# shield_mega_seed4_mpu_lobo5.net
KiCad netlist of a schematic drawn in EAGLE
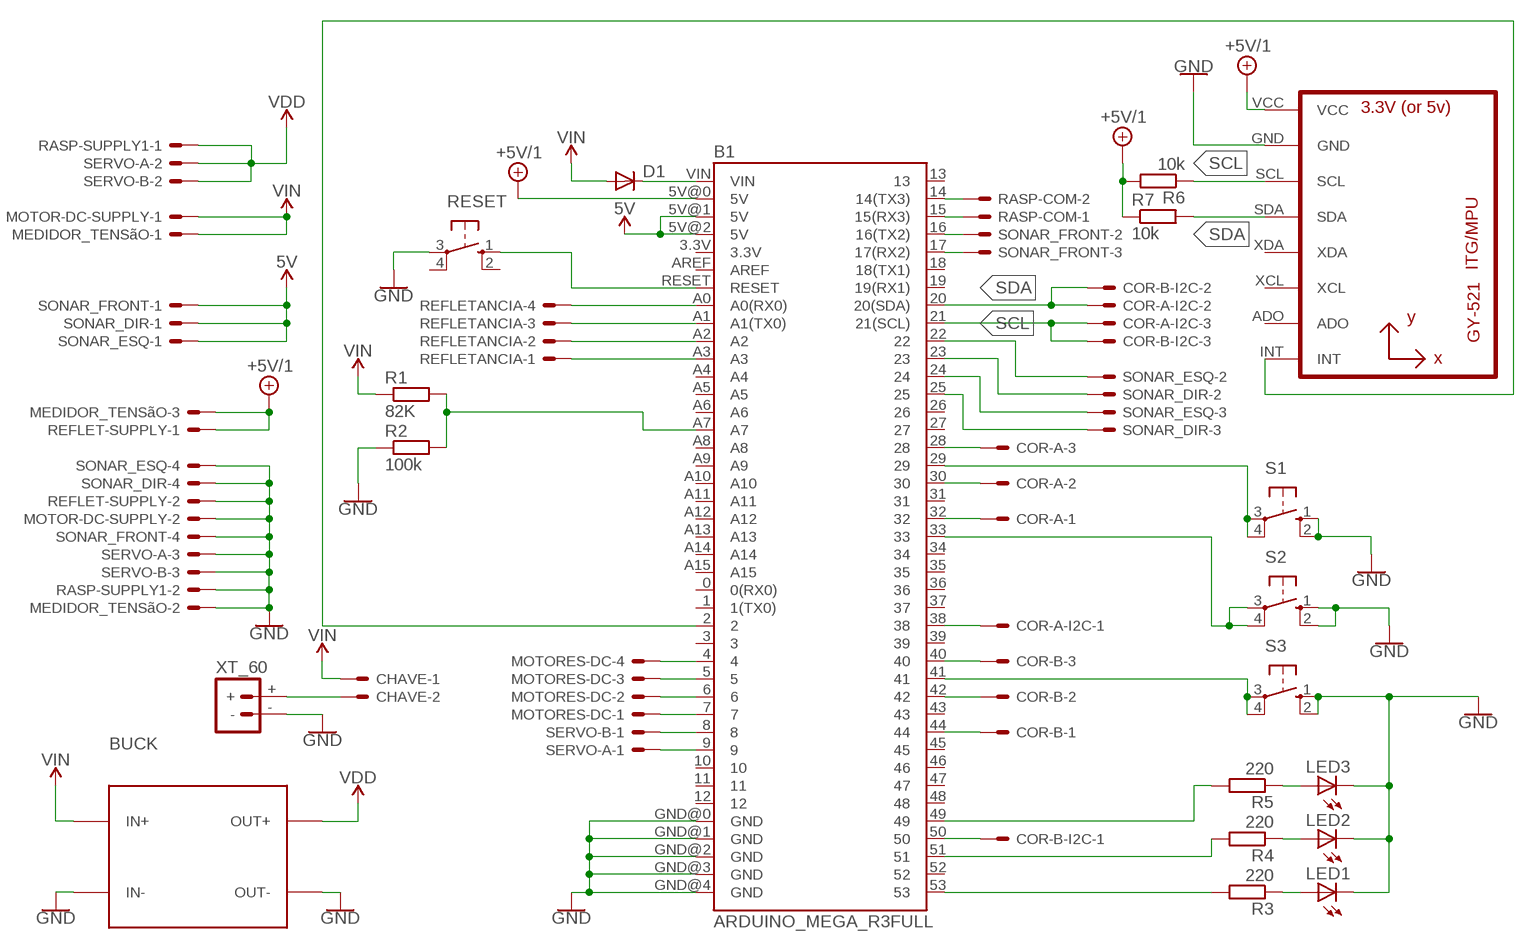
[diagram p0: schematic, sheet 1]

(export (version "E")
  (design (tool "Eeschema 10.0.6"))
  (components
    (comp (ref "B1")
      (value "ARDUINO_MEGA_R3FULL")
      (footprint "eagle-import:ARDUINO_MEGA")
      (libsource (lib "eagle-import") (part "ARDUINO_MEGA_R3FULL"))
    )
    (comp (ref "BUCK")
      (value "DC-DC-STEP-DOWN-LM2596")
      (footprint "eagle-import:DC-DC-STEP-DOWN-LM2596")
      (libsource (lib "eagle-import") (part "DC-DC-STEP-DOWN-LM2596"))
    )
    (comp (ref "CHAVE")
      (value "22-23-2021")
      (footprint "eagle-import:22-23-2021")
      (fields (field (name "MF") "MOLEX"))
      (libsource (lib "eagle-import") (part "22-23-2021"))
    )
    (comp (ref "COR-A")
      (value "22-23-2031")
      (footprint "eagle-import:22-23-2031")
      (fields (field (name "MF") "MOLEX"))
      (libsource (lib "eagle-import") (part "22-23-2031"))
    )
    (comp (ref "COR-A-I2C")
      (value "22-23-2031")
      (footprint "eagle-import:22-23-2031")
      (fields (field (name "MF") "MOLEX"))
      (libsource (lib "eagle-import") (part "22-23-2031"))
    )
    (comp (ref "COR-B")
      (value "22-23-2031")
      (footprint "eagle-import:22-23-2031")
      (fields (field (name "MF") "MOLEX"))
      (libsource (lib "eagle-import") (part "22-23-2031"))
    )
    (comp (ref "COR-B-I2C")
      (value "22-23-2031")
      (footprint "eagle-import:22-23-2031")
      (fields (field (name "MF") "MOLEX"))
      (libsource (lib "eagle-import") (part "22-23-2031"))
    )
    (comp (ref "D1")
      (value "1N4004")
      (footprint "eagle-import:DO41-10")
      (libsource (lib "eagle-import") (part "1N4004"))
    )
    (comp (ref "LED1")
      (value "LED5MM")
      (footprint "eagle-import:LED5MM")
      (libsource (lib "eagle-import") (part "LED5MM"))
    )
    (comp (ref "LED2")
      (value "LED5MM")
      (footprint "eagle-import:LED5MM")
      (libsource (lib "eagle-import") (part "LED5MM"))
    )
    (comp (ref "LED3")
      (value "LED5MM")
      (footprint "eagle-import:LED5MM")
      (libsource (lib "eagle-import") (part "LED5MM"))
    )
    (comp (ref "MEDIDOR_TENSãO")
      (value "22-23-2031")
      (footprint "eagle-import:22-23-2031")
      (fields (field (name "MF") "MOLEX"))
      (libsource (lib "eagle-import") (part "22-23-2031"))
    )
    (comp (ref "MOTOR-DC-SUPPLY")
      (value "22-23-2021")
      (footprint "eagle-import:22-23-2021")
      (fields (field (name "MF") "MOLEX"))
      (libsource (lib "eagle-import") (part "22-23-2021"))
    )
    (comp (ref "MOTORES-DC")
      (value "22-23-2041")
      (footprint "eagle-import:22-23-2041")
      (fields (field (name "MF") "MOLEX"))
      (libsource (lib "eagle-import") (part "22-23-2041"))
    )
    (comp (ref "R1")
      (value "82K")
      (footprint "eagle-import:0207_12")
      (libsource (lib "eagle-import") (part "R-EU_0207/12"))
    )
    (comp (ref "R2")
      (value "100k")
      (footprint "eagle-import:0207_12")
      (libsource (lib "eagle-import") (part "R-EU_0207/12"))
    )
    (comp (ref "R3")
      (value "220")
      (footprint "eagle-import:0207_7")
      (libsource (lib "eagle-import") (part "R-EU_0207/7"))
    )
    (comp (ref "R4")
      (value "220")
      (footprint "eagle-import:0207_7")
      (libsource (lib "eagle-import") (part "R-EU_0207/7"))
    )
    (comp (ref "R5")
      (value "220")
      (footprint "eagle-import:0207_7")
      (libsource (lib "eagle-import") (part "R-EU_0207/7"))
    )
    (comp (ref "R6")
      (value "10k")
      (footprint "eagle-import:0204_7")
      (libsource (lib "eagle-import") (part "R-EU_0204/7"))
    )
    (comp (ref "R7")
      (value "10k")
      (footprint "eagle-import:0204_7")
      (libsource (lib "eagle-import") (part "R-EU_0204/7"))
    )
    (comp (ref "RASP-COM")
      (value "22-23-2021")
      (footprint "eagle-import:22-23-2021")
      (fields (field (name "MF") "MOLEX"))
      (libsource (lib "eagle-import") (part "22-23-2021"))
    )
    (comp (ref "RASP-SUPPLY1")
      (value "22-23-2021")
      (footprint "eagle-import:22-23-2021")
      (fields (field (name "MF") "MOLEX"))
      (libsource (lib "eagle-import") (part "22-23-2021"))
    )
    (comp (ref "REFLET-SUPPLY")
      (value "22-23-2021")
      (footprint "eagle-import:22-23-2021")
      (fields (field (name "MF") "MOLEX"))
      (libsource (lib "eagle-import") (part "22-23-2021"))
    )
    (comp (ref "REFLETANCIA")
      (value "22-23-2041")
      (footprint "eagle-import:22-23-2041")
      (fields (field (name "MF") "MOLEX"))
      (libsource (lib "eagle-import") (part "22-23-2041"))
    )
    (comp (ref "RESET")
      (value "10-XX")
      (footprint "eagle-import:B3F-10XX")
      (fields (field (name "MPN") "B3F-1000"))
      (libsource (lib "eagle-import") (part "10-XX"))
    )
    (comp (ref "S1")
      (value "10-XX")
      (footprint "eagle-import:B3F-10XX")
      (fields (field (name "MPN") "B3F-1000"))
      (libsource (lib "eagle-import") (part "10-XX"))
    )
    (comp (ref "S2")
      (value "10-XX")
      (footprint "eagle-import:B3F-10XX")
      (fields (field (name "MPN") "B3F-1000"))
      (libsource (lib "eagle-import") (part "10-XX"))
    )
    (comp (ref "S3")
      (value "10-XX")
      (footprint "eagle-import:B3F-10XX")
      (fields (field (name "MPN") "B3F-1000"))
      (libsource (lib "eagle-import") (part "10-XX"))
    )
    (comp (ref "SERVO-A")
      (value "22-23-2031")
      (footprint "eagle-import:22-23-2031")
      (fields (field (name "MF") "MOLEX"))
      (libsource (lib "eagle-import") (part "22-23-2031"))
    )
    (comp (ref "SERVO-B")
      (value "22-23-2031")
      (footprint "eagle-import:22-23-2031")
      (fields (field (name "MF") "MOLEX"))
      (libsource (lib "eagle-import") (part "22-23-2031"))
    )
    (comp (ref "SONAR_DIR")
      (value "22-23-2041")
      (footprint "eagle-import:22-23-2041")
      (fields (field (name "MF") "MOLEX"))
      (libsource (lib "eagle-import") (part "22-23-2041"))
    )
    (comp (ref "SONAR_ESQ")
      (value "22-23-2041")
      (footprint "eagle-import:22-23-2041")
      (fields (field (name "MF") "MOLEX"))
      (libsource (lib "eagle-import") (part "22-23-2041"))
    )
    (comp (ref "SONAR_FRONT")
      (value "22-23-2041")
      (footprint "eagle-import:22-23-2041")
      (fields (field (name "MF") "MOLEX"))
      (libsource (lib "eagle-import") (part "22-23-2041"))
    )
    (comp (ref "U1")
      (value "GY-521MPU6050")
      (footprint "eagle-import:GY-521")
      (libsource (lib "eagle-import") (part "GY-521MPU6050"))
    )
    (comp (ref "XT_60")
      (value "BATTERY_CONNXT60")
      (footprint "eagle-import:XT60")
      (libsource (lib "eagle-import") (part "BATTERY_CONNXT60"))
    )
  )
  (nets
    (net (code "1") (name "+5V{slash}1") (class "Default")
      (node (ref "B1") (pin "5V@0") (pinfunction "5V_5V@0") (pintype "bidirectional"))
      (node (ref "MEDIDOR_TENSãO") (pin "3") (pinfunction "S_3") (pintype "passive"))
      (node (ref "R6") (pin "2") (pinfunction "2_2") (pintype "passive"))
      (node (ref "R7") (pin "1") (pinfunction "1_1") (pintype "passive"))
      (node (ref "REFLET-SUPPLY") (pin "1") (pinfunction "S_1") (pintype "passive"))
      (node (ref "U1") (pin "VCC") (pinfunction "VCC_VCC") (pintype "bidirectional"))
    )
    (net (code "2") (name "5V") (class "Default")
      (node (ref "B1") (pin "5V@1") (pinfunction "5V_5V@1") (pintype "bidirectional"))
      (node (ref "B1") (pin "5V@2") (pinfunction "5V_5V@2") (pintype "bidirectional"))
      (node (ref "SONAR_DIR") (pin "1") (pinfunction "S_1") (pintype "passive"))
      (node (ref "SONAR_ESQ") (pin "1") (pinfunction "S_1") (pintype "passive"))
      (node (ref "SONAR_FRONT") (pin "1") (pinfunction "S_1") (pintype "passive"))
    )
    (net (code "3") (name "GND") (class "Default")
      (node (ref "B1") (pin "GND@0") (pinfunction "GND_GND@0") (pintype "bidirectional"))
      (node (ref "B1") (pin "GND@1") (pinfunction "GND_GND@1") (pintype "bidirectional"))
      (node (ref "B1") (pin "GND@2") (pinfunction "GND_GND@2") (pintype "bidirectional"))
      (node (ref "B1") (pin "GND@3") (pinfunction "GND_GND@3") (pintype "bidirectional"))
      (node (ref "B1") (pin "GND@4") (pinfunction "GND_GND@4") (pintype "bidirectional"))
      (node (ref "BUCK") (pin "IN-") (pinfunction "IN-_IN-") (pintype "bidirectional"))
      (node (ref "BUCK") (pin "OUT-") (pinfunction "OUT-_OUT-") (pintype "bidirectional"))
      (node (ref "LED1") (pin "K") (pinfunction "C_K") (pintype "passive"))
      (node (ref "LED2") (pin "K") (pinfunction "C_K") (pintype "passive"))
      (node (ref "LED3") (pin "K") (pinfunction "C_K") (pintype "passive"))
      (node (ref "MEDIDOR_TENSãO") (pin "2") (pinfunction "S_2") (pintype "passive"))
      (node (ref "MOTOR-DC-SUPPLY") (pin "2") (pinfunction "S_2") (pintype "passive"))
      (node (ref "R2") (pin "1") (pinfunction "1_1") (pintype "passive"))
      (node (ref "RASP-SUPPLY1") (pin "2") (pinfunction "S_2") (pintype "passive"))
      (node (ref "REFLET-SUPPLY") (pin "2") (pinfunction "S_2") (pintype "passive"))
      (node (ref "RESET") (pin "3") (pinfunction "P_3") (pintype "passive"))
      (node (ref "S1") (pin "1") (pinfunction "S_1") (pintype "passive"))
      (node (ref "S1") (pin "2") (pinfunction "S1_2") (pintype "passive"))
      (node (ref "S2") (pin "1") (pinfunction "S_1") (pintype "passive"))
      (node (ref "S2") (pin "2") (pinfunction "S1_2") (pintype "passive"))
      (node (ref "S3") (pin "1") (pinfunction "S_1") (pintype "passive"))
      (node (ref "S3") (pin "2") (pinfunction "S1_2") (pintype "passive"))
      (node (ref "SERVO-A") (pin "3") (pinfunction "S_3") (pintype "passive"))
      (node (ref "SERVO-B") (pin "3") (pinfunction "S_3") (pintype "passive"))
      (node (ref "SONAR_DIR") (pin "4") (pinfunction "S_4") (pintype "passive"))
      (node (ref "SONAR_ESQ") (pin "4") (pinfunction "S_4") (pintype "passive"))
      (node (ref "SONAR_FRONT") (pin "4") (pinfunction "S_4") (pintype "passive"))
      (node (ref "U1") (pin "GND") (pinfunction "GND_GND") (pintype "bidirectional"))
      (node (ref "XT_60") (pin "-") (pinfunction "-_-") (pintype "passive"))
    )
    (net (code "4") (name "Net-(B1-14(TX3))") (class "Default")
      (node (ref "B1") (pin "14") (pinfunction "14(TX3)_14") (pintype "bidirectional"))
      (node (ref "RASP-COM") (pin "2") (pinfunction "S_2") (pintype "passive"))
    )
    (net (code "5") (name "Net-(B1-15(RX3))") (class "Default")
      (node (ref "B1") (pin "15") (pinfunction "15(RX3)_15") (pintype "bidirectional"))
      (node (ref "RASP-COM") (pin "1") (pinfunction "S_1") (pintype "passive"))
    )
    (net (code "6") (name "Net-(B1-16(TX2))") (class "Default")
      (node (ref "B1") (pin "16") (pinfunction "16(TX2)_16") (pintype "bidirectional"))
      (node (ref "SONAR_FRONT") (pin "2") (pinfunction "S_2") (pintype "passive"))
    )
    (net (code "7") (name "Net-(B1-17(RX2))") (class "Default")
      (node (ref "B1") (pin "17") (pinfunction "17(RX2)_17") (pintype "bidirectional"))
      (node (ref "SONAR_FRONT") (pin "3") (pinfunction "S_3") (pintype "passive"))
    )
    (net (code "8") (name "Net-(B1-A0(RX0))") (class "Default")
      (node (ref "B1") (pin "A0") (pinfunction "A0(RX0)_A0") (pintype "bidirectional"))
      (node (ref "REFLETANCIA") (pin "4") (pinfunction "S_4") (pintype "passive"))
    )
    (net (code "9") (name "Net-(B1-A1(TX0))") (class "Default")
      (node (ref "B1") (pin "A1") (pinfunction "A1(TX0)_A1") (pintype "bidirectional"))
      (node (ref "REFLETANCIA") (pin "3") (pinfunction "S_3") (pintype "passive"))
    )
    (net (code "10") (name "Net-(B1-Pad2)") (class "Default")
      (node (ref "B1") (pin "2") (pinfunction "2_2") (pintype "bidirectional"))
      (node (ref "U1") (pin "INT") (pinfunction "INT_INT") (pintype "bidirectional"))
    )
    (net (code "11") (name "Net-(B1-Pad49)") (class "Default")
      (node (ref "B1") (pin "49") (pinfunction "49_49") (pintype "bidirectional"))
      (node (ref "R5") (pin "2") (pinfunction "2_2") (pintype "passive"))
    )
    (net (code "12") (name "Net-(B1-Pad51)") (class "Default")
      (node (ref "B1") (pin "51") (pinfunction "51_51") (pintype "bidirectional"))
      (node (ref "R4") (pin "2") (pinfunction "2_2") (pintype "passive"))
    )
    (net (code "13") (name "Net-(B1-Pad53)") (class "Default")
      (node (ref "B1") (pin "53") (pinfunction "53_53") (pintype "bidirectional"))
      (node (ref "R3") (pin "2") (pinfunction "2_2") (pintype "passive"))
    )
    (net (code "14") (name "Net-(B1-PadA7)") (class "Default")
      (node (ref "B1") (pin "A7") (pinfunction "A7_A7") (pintype "bidirectional"))
      (node (ref "R1") (pin "2") (pinfunction "2_2") (pintype "passive"))
      (node (ref "R2") (pin "2") (pinfunction "2_2") (pintype "passive"))
    )
    (net (code "15") (name "Net-(B1-PadVIN)") (class "Default")
      (node (ref "B1") (pin "VIN") (pinfunction "VIN_VIN") (pintype "bidirectional"))
      (node (ref "D1") (pin "C") (pinfunction "C_C") (pintype "passive"))
    )
    (net (code "16") (name "Net-(CHAVEB-S)") (class "Default")
      (node (ref "CHAVE") (pin "2") (pinfunction "S_2") (pintype "passive"))
      (node (ref "XT_60") (pin "+") (pinfunction "+_+") (pintype "passive"))
    )
    (net (code "17") (name "Net-(COR-A-I2CA-S)") (class "Default")
      (node (ref "B1") (pin "38") (pinfunction "38_38") (pintype "bidirectional"))
      (node (ref "COR-A-I2C") (pin "1") (pinfunction "S_1") (pintype "passive"))
    )
    (net (code "18") (name "Net-(COR-AA-S)") (class "Default")
      (node (ref "B1") (pin "32") (pinfunction "32_32") (pintype "bidirectional"))
      (node (ref "COR-A") (pin "1") (pinfunction "S_1") (pintype "passive"))
    )
    (net (code "19") (name "Net-(COR-AB-S)") (class "Default")
      (node (ref "B1") (pin "30") (pinfunction "30_30") (pintype "bidirectional"))
      (node (ref "COR-A") (pin "2") (pinfunction "S_2") (pintype "passive"))
    )
    (net (code "20") (name "Net-(COR-AC-S)") (class "Default")
      (node (ref "B1") (pin "28") (pinfunction "28_28") (pintype "bidirectional"))
      (node (ref "COR-A") (pin "3") (pinfunction "S_3") (pintype "passive"))
    )
    (net (code "21") (name "Net-(COR-B-I2CA-S)") (class "Default")
      (node (ref "B1") (pin "50") (pinfunction "50_50") (pintype "bidirectional"))
      (node (ref "COR-B-I2C") (pin "1") (pinfunction "S_1") (pintype "passive"))
    )
    (net (code "22") (name "Net-(COR-BA-S)") (class "Default")
      (node (ref "B1") (pin "44") (pinfunction "44_44") (pintype "bidirectional"))
      (node (ref "COR-B") (pin "1") (pinfunction "S_1") (pintype "passive"))
    )
    (net (code "23") (name "Net-(COR-BB-S)") (class "Default")
      (node (ref "B1") (pin "42") (pinfunction "42_42") (pintype "bidirectional"))
      (node (ref "COR-B") (pin "2") (pinfunction "S_2") (pintype "passive"))
    )
    (net (code "24") (name "Net-(COR-BC-S)") (class "Default")
      (node (ref "B1") (pin "40") (pinfunction "40_40") (pintype "bidirectional"))
      (node (ref "COR-B") (pin "3") (pinfunction "S_3") (pintype "passive"))
    )
    (net (code "25") (name "Net-(LED1-PadA)") (class "Default")
      (node (ref "LED1") (pin "A") (pinfunction "A_A") (pintype "passive"))
      (node (ref "R3") (pin "1") (pinfunction "1_1") (pintype "passive"))
    )
    (net (code "26") (name "Net-(LED2-PadA)") (class "Default")
      (node (ref "LED2") (pin "A") (pinfunction "A_A") (pintype "passive"))
      (node (ref "R4") (pin "1") (pinfunction "1_1") (pintype "passive"))
    )
    (net (code "27") (name "Net-(LED3-PadA)") (class "Default")
      (node (ref "LED3") (pin "A") (pinfunction "A_A") (pintype "passive"))
      (node (ref "R5") (pin "1") (pinfunction "1_1") (pintype "passive"))
    )
    (net (code "28") (name "Net-(MOTORES-DCA-S)") (class "Default")
      (node (ref "B1") (pin "7") (pinfunction "7_7") (pintype "bidirectional"))
      (node (ref "MOTORES-DC") (pin "1") (pinfunction "S_1") (pintype "passive"))
    )
    (net (code "29") (name "Net-(MOTORES-DCB-S)") (class "Default")
      (node (ref "B1") (pin "6") (pinfunction "6_6") (pintype "bidirectional"))
      (node (ref "MOTORES-DC") (pin "2") (pinfunction "S_2") (pintype "passive"))
    )
    (net (code "30") (name "Net-(MOTORES-DCC-S)") (class "Default")
      (node (ref "B1") (pin "5") (pinfunction "5_5") (pintype "bidirectional"))
      (node (ref "MOTORES-DC") (pin "3") (pinfunction "S_3") (pintype "passive"))
    )
    (net (code "31") (name "Net-(MOTORES-DCD-S)") (class "Default")
      (node (ref "B1") (pin "4") (pinfunction "4_4") (pintype "bidirectional"))
      (node (ref "MOTORES-DC") (pin "4") (pinfunction "S_4") (pintype "passive"))
    )
    (net (code "32") (name "Net-(REFLETANCIAA-S)") (class "Default")
      (node (ref "B1") (pin "A3") (pinfunction "A3_A3") (pintype "bidirectional"))
      (node (ref "REFLETANCIA") (pin "1") (pinfunction "S_1") (pintype "passive"))
    )
    (net (code "33") (name "Net-(REFLETANCIAB-S)") (class "Default")
      (node (ref "B1") (pin "A2") (pinfunction "A2_A2") (pintype "bidirectional"))
      (node (ref "REFLETANCIA") (pin "2") (pinfunction "S_2") (pintype "passive"))
    )
    (net (code "34") (name "Net-(RESET-S)") (class "Default")
      (node (ref "B1") (pin "RESET") (pinfunction "RESET_RESET") (pintype "bidirectional"))
      (node (ref "RESET") (pin "1") (pinfunction "S_1") (pintype "passive"))
    )
    (net (code "35") (name "Net-(S1-P)") (class "Default")
      (node (ref "B1") (pin "29") (pinfunction "29_29") (pintype "bidirectional"))
      (node (ref "S1") (pin "3") (pinfunction "P_3") (pintype "passive"))
      (node (ref "S1") (pin "4") (pinfunction "P1_4") (pintype "passive"))
    )
    (net (code "36") (name "Net-(S2-P)") (class "Default")
      (node (ref "B1") (pin "33") (pinfunction "33_33") (pintype "bidirectional"))
      (node (ref "S2") (pin "3") (pinfunction "P_3") (pintype "passive"))
      (node (ref "S2") (pin "4") (pinfunction "P1_4") (pintype "passive"))
    )
    (net (code "37") (name "Net-(S3-P)") (class "Default")
      (node (ref "B1") (pin "41") (pinfunction "41_41") (pintype "bidirectional"))
      (node (ref "S3") (pin "3") (pinfunction "P_3") (pintype "passive"))
      (node (ref "S3") (pin "4") (pinfunction "P1_4") (pintype "passive"))
    )
    (net (code "38") (name "Net-(SERVO-AA-S)") (class "Default")
      (node (ref "B1") (pin "9") (pinfunction "9_9") (pintype "bidirectional"))
      (node (ref "SERVO-A") (pin "1") (pinfunction "S_1") (pintype "passive"))
    )
    (net (code "39") (name "Net-(SERVO-BA-S)") (class "Default")
      (node (ref "B1") (pin "8") (pinfunction "8_8") (pintype "bidirectional"))
      (node (ref "SERVO-B") (pin "1") (pinfunction "S_1") (pintype "passive"))
    )
    (net (code "40") (name "Net-(SONAR_DIRB-S)") (class "Default")
      (node (ref "B1") (pin "23") (pinfunction "23_23") (pintype "bidirectional"))
      (node (ref "SONAR_DIR") (pin "2") (pinfunction "S_2") (pintype "passive"))
    )
    (net (code "41") (name "Net-(SONAR_DIRC-S)") (class "Default")
      (node (ref "B1") (pin "25") (pinfunction "25_25") (pintype "bidirectional"))
      (node (ref "SONAR_DIR") (pin "3") (pinfunction "S_3") (pintype "passive"))
    )
    (net (code "42") (name "Net-(SONAR_ESQB-S)") (class "Default")
      (node (ref "B1") (pin "22") (pinfunction "22_22") (pintype "bidirectional"))
      (node (ref "SONAR_ESQ") (pin "2") (pinfunction "S_2") (pintype "passive"))
    )
    (net (code "43") (name "Net-(SONAR_ESQC-S)") (class "Default")
      (node (ref "B1") (pin "24") (pinfunction "24_24") (pintype "bidirectional"))
      (node (ref "SONAR_ESQ") (pin "3") (pinfunction "S_3") (pintype "passive"))
    )
    (net (code "44") (name "SCL") (class "Default")
      (node (ref "B1") (pin "21") (pinfunction "21(SCL)_21") (pintype "bidirectional"))
      (node (ref "COR-A-I2C") (pin "3") (pinfunction "S_3") (pintype "passive"))
      (node (ref "COR-B-I2C") (pin "3") (pinfunction "S_3") (pintype "passive"))
      (node (ref "R6") (pin "1") (pinfunction "1_1") (pintype "passive"))
      (node (ref "U1") (pin "SCL") (pinfunction "SCL_SCL") (pintype "bidirectional"))
    )
    (net (code "45") (name "SDA") (class "Default")
      (node (ref "B1") (pin "20") (pinfunction "20(SDA)_20") (pintype "bidirectional"))
      (node (ref "COR-A-I2C") (pin "2") (pinfunction "S_2") (pintype "passive"))
      (node (ref "COR-B-I2C") (pin "2") (pinfunction "S_2") (pintype "passive"))
      (node (ref "R7") (pin "2") (pinfunction "2_2") (pintype "passive"))
      (node (ref "U1") (pin "SDA") (pinfunction "SDA_SDA") (pintype "bidirectional"))
    )
    (net (code "46") (name "VDD") (class "Default")
      (node (ref "BUCK") (pin "OUT+") (pinfunction "OUT+_OUT+") (pintype "bidirectional"))
      (node (ref "RASP-SUPPLY1") (pin "1") (pinfunction "S_1") (pintype "passive"))
      (node (ref "SERVO-A") (pin "2") (pinfunction "S_2") (pintype "passive"))
      (node (ref "SERVO-B") (pin "2") (pinfunction "S_2") (pintype "passive"))
    )
    (net (code "47") (name "VIN") (class "Default")
      (node (ref "BUCK") (pin "IN+") (pinfunction "IN+_IN+") (pintype "bidirectional"))
      (node (ref "CHAVE") (pin "1") (pinfunction "S_1") (pintype "passive"))
      (node (ref "D1") (pin "A") (pinfunction "A_A") (pintype "passive"))
      (node (ref "MEDIDOR_TENSãO") (pin "1") (pinfunction "S_1") (pintype "passive"))
      (node (ref "MOTOR-DC-SUPPLY") (pin "1") (pinfunction "S_1") (pintype "passive"))
      (node (ref "R1") (pin "1") (pinfunction "1_1") (pintype "passive"))
    )
    (net (code "48") (name "unconnected-(B1-0(RX0)-Pad0)") (class "Default")
      (node (ref "B1") (pin "0") (pinfunction "0(RX0)_0") (pintype "bidirectional"))
    )
    (net (code "49") (name "unconnected-(B1-1(TX0)-Pad1)") (class "Default")
      (node (ref "B1") (pin "1") (pinfunction "1(TX0)_1") (pintype "bidirectional"))
    )
    (net (code "50") (name "unconnected-(B1-18(TX1)-Pad18)") (class "Default")
      (node (ref "B1") (pin "18") (pinfunction "18(TX1)_18") (pintype "bidirectional"))
    )
    (net (code "51") (name "unconnected-(B1-19(RX1)-Pad19)") (class "Default")
      (node (ref "B1") (pin "19") (pinfunction "19(RX1)_19") (pintype "bidirectional"))
    )
    (net (code "52") (name "unconnected-(B1-Pad3)") (class "Default")
      (node (ref "B1") (pin "3") (pinfunction "3_3") (pintype "bidirectional"))
    )
    (net (code "53") (name "unconnected-(B1-Pad3.3V)") (class "Default")
      (node (ref "B1") (pin "3.3V") (pinfunction "3.3V_3.3V") (pintype "bidirectional"))
    )
    (net (code "54") (name "unconnected-(B1-Pad10)") (class "Default")
      (node (ref "B1") (pin "10") (pinfunction "10_10") (pintype "bidirectional"))
    )
    (net (code "55") (name "unconnected-(B1-Pad11)") (class "Default")
      (node (ref "B1") (pin "11") (pinfunction "11_11") (pintype "bidirectional"))
    )
    (net (code "56") (name "unconnected-(B1-Pad12)") (class "Default")
      (node (ref "B1") (pin "12") (pinfunction "12_12") (pintype "bidirectional"))
    )
    (net (code "57") (name "unconnected-(B1-Pad13)") (class "Default")
      (node (ref "B1") (pin "13") (pinfunction "13_13") (pintype "bidirectional"))
    )
    (net (code "58") (name "unconnected-(B1-Pad26)") (class "Default")
      (node (ref "B1") (pin "26") (pinfunction "26_26") (pintype "bidirectional"))
    )
    (net (code "59") (name "unconnected-(B1-Pad27)") (class "Default")
      (node (ref "B1") (pin "27") (pinfunction "27_27") (pintype "bidirectional"))
    )
    (net (code "60") (name "unconnected-(B1-Pad31)") (class "Default")
      (node (ref "B1") (pin "31") (pinfunction "31_31") (pintype "bidirectional"))
    )
    (net (code "61") (name "unconnected-(B1-Pad34)") (class "Default")
      (node (ref "B1") (pin "34") (pinfunction "34_34") (pintype "bidirectional"))
    )
    (net (code "62") (name "unconnected-(B1-Pad35)") (class "Default")
      (node (ref "B1") (pin "35") (pinfunction "35_35") (pintype "bidirectional"))
    )
    (net (code "63") (name "unconnected-(B1-Pad36)") (class "Default")
      (node (ref "B1") (pin "36") (pinfunction "36_36") (pintype "bidirectional"))
    )
    (net (code "64") (name "unconnected-(B1-Pad37)") (class "Default")
      (node (ref "B1") (pin "37") (pinfunction "37_37") (pintype "bidirectional"))
    )
    (net (code "65") (name "unconnected-(B1-Pad39)") (class "Default")
      (node (ref "B1") (pin "39") (pinfunction "39_39") (pintype "bidirectional"))
    )
    (net (code "66") (name "unconnected-(B1-Pad43)") (class "Default")
      (node (ref "B1") (pin "43") (pinfunction "43_43") (pintype "bidirectional"))
    )
    (net (code "67") (name "unconnected-(B1-Pad45)") (class "Default")
      (node (ref "B1") (pin "45") (pinfunction "45_45") (pintype "bidirectional"))
    )
    (net (code "68") (name "unconnected-(B1-Pad46)") (class "Default")
      (node (ref "B1") (pin "46") (pinfunction "46_46") (pintype "bidirectional"))
    )
    (net (code "69") (name "unconnected-(B1-Pad47)") (class "Default")
      (node (ref "B1") (pin "47") (pinfunction "47_47") (pintype "bidirectional"))
    )
    (net (code "70") (name "unconnected-(B1-Pad48)") (class "Default")
      (node (ref "B1") (pin "48") (pinfunction "48_48") (pintype "bidirectional"))
    )
    (net (code "71") (name "unconnected-(B1-Pad52)") (class "Default")
      (node (ref "B1") (pin "52") (pinfunction "52_52") (pintype "bidirectional"))
    )
    (net (code "72") (name "unconnected-(B1-PadA4)") (class "Default")
      (node (ref "B1") (pin "A4") (pinfunction "A4_A4") (pintype "bidirectional"))
    )
    (net (code "73") (name "unconnected-(B1-PadA5)") (class "Default")
      (node (ref "B1") (pin "A5") (pinfunction "A5_A5") (pintype "bidirectional"))
    )
    (net (code "74") (name "unconnected-(B1-PadA6)") (class "Default")
      (node (ref "B1") (pin "A6") (pinfunction "A6_A6") (pintype "bidirectional"))
    )
    (net (code "75") (name "unconnected-(B1-PadA8)") (class "Default")
      (node (ref "B1") (pin "A8") (pinfunction "A8_A8") (pintype "bidirectional"))
    )
    (net (code "76") (name "unconnected-(B1-PadA9)") (class "Default")
      (node (ref "B1") (pin "A9") (pinfunction "A9_A9") (pintype "bidirectional"))
    )
    (net (code "77") (name "unconnected-(B1-PadA10)") (class "Default")
      (node (ref "B1") (pin "A10") (pinfunction "A10_A10") (pintype "bidirectional"))
    )
    (net (code "78") (name "unconnected-(B1-PadA11)") (class "Default")
      (node (ref "B1") (pin "A11") (pinfunction "A11_A11") (pintype "bidirectional"))
    )
    (net (code "79") (name "unconnected-(B1-PadA12)") (class "Default")
      (node (ref "B1") (pin "A12") (pinfunction "A12_A12") (pintype "bidirectional"))
    )
    (net (code "80") (name "unconnected-(B1-PadA13)") (class "Default")
      (node (ref "B1") (pin "A13") (pinfunction "A13_A13") (pintype "bidirectional"))
    )
    (net (code "81") (name "unconnected-(B1-PadA14)") (class "Default")
      (node (ref "B1") (pin "A14") (pinfunction "A14_A14") (pintype "bidirectional"))
    )
    (net (code "82") (name "unconnected-(B1-PadA15)") (class "Default")
      (node (ref "B1") (pin "A15") (pinfunction "A15_A15") (pintype "bidirectional"))
    )
    (net (code "83") (name "unconnected-(B1-PadAREF)") (class "Default")
      (node (ref "B1") (pin "AREF") (pinfunction "AREF_AREF") (pintype "bidirectional"))
    )
    (net (code "84") (name "unconnected-(RESET-P1-Pad4)") (class "Default")
      (node (ref "RESET") (pin "4") (pinfunction "P1_4") (pintype "passive"))
    )
    (net (code "85") (name "unconnected-(RESET-S1-Pad2)") (class "Default")
      (node (ref "RESET") (pin "2") (pinfunction "S1_2") (pintype "passive"))
    )
    (net (code "86") (name "unconnected-(U1-PadADO)") (class "Default")
      (node (ref "U1") (pin "ADO") (pinfunction "ADO_ADO") (pintype "bidirectional"))
    )
    (net (code "87") (name "unconnected-(U1-PadXCL)") (class "Default")
      (node (ref "U1") (pin "XCL") (pinfunction "XCL_XCL") (pintype "bidirectional"))
    )
    (net (code "88") (name "unconnected-(U1-PadXDA)") (class "Default")
      (node (ref "U1") (pin "XDA") (pinfunction "XDA_XDA") (pintype "bidirectional"))
    )
  )
)
